# schema.net
KiCad netlist of a schematic drawn in Altium Designer
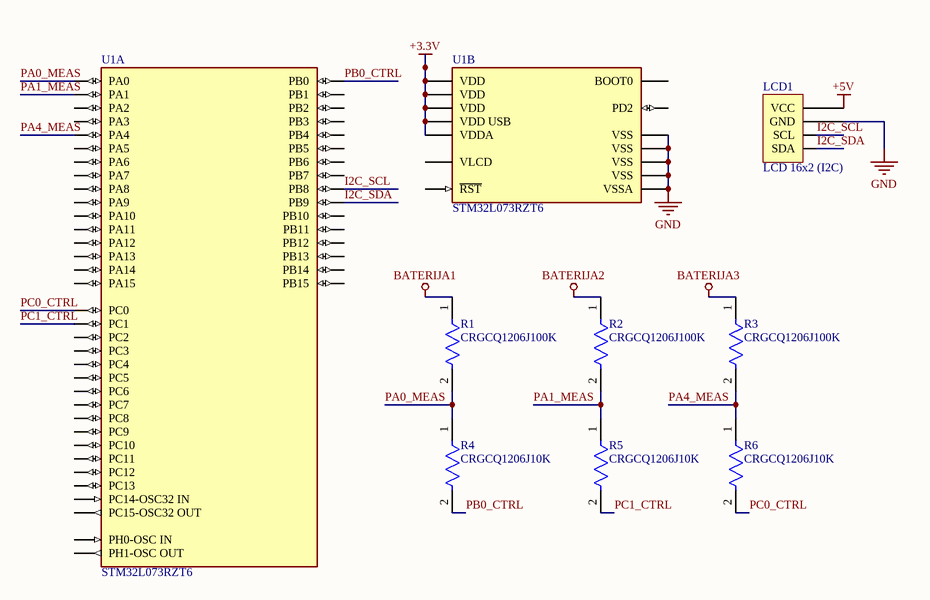
[diagram p0: schema.SchDoc]

(export (version "E")
  (design (tool "Eeschema 10.0.6"))
  (components
    (comp (ref "LCD1") (value "LCD 16x2 (I2C)") (libsource (lib "LCD") (part "LCD_I2C")))
    (comp (ref "R1")
      (value "CRGCQ1206J100K")
      (footprint "FP-CRGCQ1206-IPC_C")
      (description "CRGCQ1206 100KΩ 0.25W 5% ±100ppm/°C 200V")
      (fields
        (field (name "OCTOPART") "https://octopart.com/crgcq1206j100k-te+connectivity-91018303")
        (field (name "MANUFACTURER") "TE Connectivity")
      )
      (libsource (lib "Altium Content Vault") (part "1029c3af85768c4190bb7ad29bc67b5"))
    )
    (comp (ref "R2")
      (value "CRGCQ1206J100K")
      (footprint "FP-CRGCQ1206-IPC_C")
      (description "CRGCQ1206 100KΩ 0.25W 5% ±100ppm/°C 200V")
      (fields
        (field (name "OCTOPART") "https://octopart.com/crgcq1206j100k-te+connectivity-91018303")
        (field (name "MANUFACTURER") "TE Connectivity")
      )
      (libsource (lib "Altium Content Vault") (part "1029c3af85768c4190bb7ad29bc67b5"))
    )
    (comp (ref "R3")
      (value "CRGCQ1206J100K")
      (footprint "FP-CRGCQ1206-IPC_C")
      (description "CRGCQ1206 100KΩ 0.25W 5% ±100ppm/°C 200V")
      (fields
        (field (name "OCTOPART") "https://octopart.com/crgcq1206j100k-te+connectivity-91018303")
        (field (name "MANUFACTURER") "TE Connectivity")
      )
      (libsource (lib "Altium Content Vault") (part "1029c3af85768c4190bb7ad29bc67b5"))
    )
    (comp (ref "R4")
      (value "CRGCQ1206J10K")
      (footprint "FP-CRGCQ1206-IPC_C")
      (description "CRGCQ1206 10KΩ 0.25W 5% ±100ppm/°C 200V")
      (fields (field (name "MANUFACTURER") "TE Connectivity") (field (name "TOLERANCE") "0.05"))
      (libsource (lib "Altium Content Vault") (part "1029c3af85768c4190bb7ad29bc67b5"))
    )
    (comp (ref "R5")
      (value "CRGCQ1206J10K")
      (footprint "FP-CRGCQ1206-IPC_C")
      (description "CRGCQ1206 10KΩ 0.25W 5% ±100ppm/°C 200V")
      (fields (field (name "MANUFACTURER") "TE Connectivity") (field (name "TOLERANCE") "0.05"))
      (libsource (lib "Altium Content Vault") (part "1029c3af85768c4190bb7ad29bc67b5"))
    )
    (comp (ref "R6")
      (value "CRGCQ1206J10K")
      (footprint "FP-CRGCQ1206-IPC_C")
      (description "CRGCQ1206 10KΩ 0.25W 5% ±100ppm/°C 200V")
      (fields (field (name "MANUFACTURER") "TE Connectivity") (field (name "TOLERANCE") "0.05"))
      (libsource (lib "Altium Content Vault") (part "1029c3af85768c4190bb7ad29bc67b5"))
    )
    (comp (ref "U1")
      (value "STM32L073RZT6")
      (footprint "FP-LQFP64-5W-MFG")
      (description "IC MCU 32BIT 192KB FLASH 64LQFP")
      (libsource (lib "Altium Content Vault") (part "4466eda20ed5015702b21cb01f06cb7"))
    )
  )
  (nets
    (net (code "1") (name "+3.3V") (class "Default")
      (node (ref "U1") (pin "13") (pinfunction "VDDA_13") (pintype "power_in"))
      (node (ref "U1") (pin "19") (pinfunction "VDD_19") (pintype "power_in"))
      (node (ref "U1") (pin "32") (pinfunction "VDD_32") (pintype "power_in"))
      (node (ref "U1") (pin "48") (pinfunction "VDD_USB_48") (pintype "power_in"))
      (node (ref "U1") (pin "64") (pinfunction "VDD_64") (pintype "power_in"))
    )
    (net (code "2") (name "+5V") (class "Default")
      (node (ref "LCD1") (pin "1") (pinfunction "VCC_1") (pintype "passive"))
    )
    (net (code "3") (name "/I2C_SCL") (class "Default")
      (node (ref "LCD1") (pin "3") (pinfunction "SCL_3") (pintype "passive"))
      (node (ref "U1") (pin "61") (pinfunction "PB8_61") (pintype "bidirectional"))
    )
    (net (code "4") (name "/I2C_SDA") (class "Default")
      (node (ref "LCD1") (pin "4") (pinfunction "SDA_4") (pintype "passive"))
      (node (ref "U1") (pin "62") (pinfunction "PB9_62") (pintype "bidirectional"))
    )
    (net (code "5") (name "/PA0_MEAS") (class "Default")
      (node (ref "R1") (pin "2") (pinfunction "2_2") (pintype "passive"))
      (node (ref "R4") (pin "1") (pinfunction "1_1") (pintype "passive"))
      (node (ref "U1") (pin "14") (pinfunction "PA0_14") (pintype "bidirectional"))
    )
    (net (code "6") (name "/PA1_MEAS") (class "Default")
      (node (ref "R2") (pin "2") (pinfunction "2_2") (pintype "passive"))
      (node (ref "R5") (pin "1") (pinfunction "1_1") (pintype "passive"))
      (node (ref "U1") (pin "15") (pinfunction "PA1_15") (pintype "bidirectional"))
    )
    (net (code "7") (name "/PA4_MEAS") (class "Default")
      (node (ref "R3") (pin "2") (pinfunction "2_2") (pintype "passive"))
      (node (ref "R6") (pin "1") (pinfunction "1_1") (pintype "passive"))
      (node (ref "U1") (pin "20") (pinfunction "PA4_20") (pintype "bidirectional"))
    )
    (net (code "8") (name "/PB0_CTRL") (class "Default")
      (node (ref "R4") (pin "2") (pinfunction "2_2") (pintype "passive"))
      (node (ref "U1") (pin "26") (pinfunction "PB0_26") (pintype "bidirectional"))
    )
    (net (code "9") (name "/PC0_CTRL") (class "Default")
      (node (ref "R6") (pin "2") (pinfunction "2_2") (pintype "passive"))
      (node (ref "U1") (pin "8") (pinfunction "PC0_8") (pintype "bidirectional"))
    )
    (net (code "10") (name "/PC1_CTRL") (class "Default")
      (node (ref "R5") (pin "2") (pinfunction "2_2") (pintype "passive"))
      (node (ref "U1") (pin "9") (pinfunction "PC1_9") (pintype "bidirectional"))
    )
    (net (code "11") (name "BATERIJA1") (class "Default")
      (node (ref "R1") (pin "1") (pinfunction "1_1") (pintype "passive"))
    )
    (net (code "12") (name "BATERIJA2") (class "Default")
      (node (ref "R2") (pin "1") (pinfunction "1_1") (pintype "passive"))
    )
    (net (code "13") (name "BATERIJA3") (class "Default")
      (node (ref "R3") (pin "1") (pinfunction "1_1") (pintype "passive"))
    )
    (net (code "14") (name "GND") (class "Default")
      (node (ref "LCD1") (pin "2") (pinfunction "GND_2") (pintype "passive"))
      (node (ref "U1") (pin "12") (pinfunction "VSSA_12") (pintype "power_in"))
      (node (ref "U1") (pin "18") (pinfunction "VSS_18") (pintype "power_in"))
      (node (ref "U1") (pin "31") (pinfunction "VSS_31") (pintype "power_in"))
      (node (ref "U1") (pin "47") (pinfunction "VSS_47") (pintype "power_in"))
      (node (ref "U1") (pin "63") (pinfunction "VSS_63") (pintype "power_in"))
    )
    (net (code "15") (name "unconnected-(U1A-PA2-Pad16)") (class "Default")
      (node (ref "U1") (pin "16") (pinfunction "PA2_16") (pintype "bidirectional"))
    )
    (net (code "16") (name "unconnected-(U1A-PA3-Pad17)") (class "Default")
      (node (ref "U1") (pin "17") (pinfunction "PA3_17") (pintype "bidirectional"))
    )
    (net (code "17") (name "unconnected-(U1A-PA5-Pad21)") (class "Default")
      (node (ref "U1") (pin "21") (pinfunction "PA5_21") (pintype "bidirectional"))
    )
    (net (code "18") (name "unconnected-(U1A-PA6-Pad22)") (class "Default")
      (node (ref "U1") (pin "22") (pinfunction "PA6_22") (pintype "bidirectional"))
    )
    (net (code "19") (name "unconnected-(U1A-PA7-Pad23)") (class "Default")
      (node (ref "U1") (pin "23") (pinfunction "PA7_23") (pintype "bidirectional"))
    )
    (net (code "20") (name "unconnected-(U1A-PA8-Pad41)") (class "Default")
      (node (ref "U1") (pin "41") (pinfunction "PA8_41") (pintype "bidirectional"))
    )
    (net (code "21") (name "unconnected-(U1A-PA9-Pad42)") (class "Default")
      (node (ref "U1") (pin "42") (pinfunction "PA9_42") (pintype "bidirectional"))
    )
    (net (code "22") (name "unconnected-(U1A-PA10-Pad43)") (class "Default")
      (node (ref "U1") (pin "43") (pinfunction "PA10_43") (pintype "bidirectional"))
    )
    (net (code "23") (name "unconnected-(U1A-PA11-Pad44)") (class "Default")
      (node (ref "U1") (pin "44") (pinfunction "PA11_44") (pintype "bidirectional"))
    )
    (net (code "24") (name "unconnected-(U1A-PA12-Pad45)") (class "Default")
      (node (ref "U1") (pin "45") (pinfunction "PA12_45") (pintype "bidirectional"))
    )
    (net (code "25") (name "unconnected-(U1A-PA13-Pad46)") (class "Default")
      (node (ref "U1") (pin "46") (pinfunction "PA13_46") (pintype "bidirectional"))
    )
    (net (code "26") (name "unconnected-(U1A-PA14-Pad49)") (class "Default")
      (node (ref "U1") (pin "49") (pinfunction "PA14_49") (pintype "bidirectional"))
    )
    (net (code "27") (name "unconnected-(U1A-PA15-Pad50)") (class "Default")
      (node (ref "U1") (pin "50") (pinfunction "PA15_50") (pintype "bidirectional"))
    )
    (net (code "28") (name "unconnected-(U1A-PB1-Pad27)") (class "Default")
      (node (ref "U1") (pin "27") (pinfunction "PB1_27") (pintype "bidirectional"))
    )
    (net (code "29") (name "unconnected-(U1A-PB2-Pad28)") (class "Default")
      (node (ref "U1") (pin "28") (pinfunction "PB2_28") (pintype "bidirectional"))
    )
    (net (code "30") (name "unconnected-(U1A-PB3-Pad55)") (class "Default")
      (node (ref "U1") (pin "55") (pinfunction "PB3_55") (pintype "bidirectional"))
    )
    (net (code "31") (name "unconnected-(U1A-PB4-Pad56)") (class "Default")
      (node (ref "U1") (pin "56") (pinfunction "PB4_56") (pintype "bidirectional"))
    )
    (net (code "32") (name "unconnected-(U1A-PB5-Pad57)") (class "Default")
      (node (ref "U1") (pin "57") (pinfunction "PB5_57") (pintype "bidirectional"))
    )
    (net (code "33") (name "unconnected-(U1A-PB6-Pad58)") (class "Default")
      (node (ref "U1") (pin "58") (pinfunction "PB6_58") (pintype "bidirectional"))
    )
    (net (code "34") (name "unconnected-(U1A-PB7-Pad59)") (class "Default")
      (node (ref "U1") (pin "59") (pinfunction "PB7_59") (pintype "bidirectional"))
    )
    (net (code "35") (name "unconnected-(U1A-PB10-Pad29)") (class "Default")
      (node (ref "U1") (pin "29") (pinfunction "PB10_29") (pintype "bidirectional"))
    )
    (net (code "36") (name "unconnected-(U1A-PB11-Pad30)") (class "Default")
      (node (ref "U1") (pin "30") (pinfunction "PB11_30") (pintype "bidirectional"))
    )
    (net (code "37") (name "unconnected-(U1A-PB12-Pad33)") (class "Default")
      (node (ref "U1") (pin "33") (pinfunction "PB12_33") (pintype "bidirectional"))
    )
    (net (code "38") (name "unconnected-(U1A-PB13-Pad34)") (class "Default")
      (node (ref "U1") (pin "34") (pinfunction "PB13_34") (pintype "bidirectional"))
    )
    (net (code "39") (name "unconnected-(U1A-PB14-Pad35)") (class "Default")
      (node (ref "U1") (pin "35") (pinfunction "PB14_35") (pintype "bidirectional"))
    )
    (net (code "40") (name "unconnected-(U1A-PB15-Pad36)") (class "Default")
      (node (ref "U1") (pin "36") (pinfunction "PB15_36") (pintype "bidirectional"))
    )
    (net (code "41") (name "unconnected-(U1A-PC2-Pad10)") (class "Default")
      (node (ref "U1") (pin "10") (pinfunction "PC2_10") (pintype "bidirectional"))
    )
    (net (code "42") (name "unconnected-(U1A-PC3-Pad11)") (class "Default")
      (node (ref "U1") (pin "11") (pinfunction "PC3_11") (pintype "bidirectional"))
    )
    (net (code "43") (name "unconnected-(U1A-PC4-Pad24)") (class "Default")
      (node (ref "U1") (pin "24") (pinfunction "PC4_24") (pintype "bidirectional"))
    )
    (net (code "44") (name "unconnected-(U1A-PC5-Pad25)") (class "Default")
      (node (ref "U1") (pin "25") (pinfunction "PC5_25") (pintype "bidirectional"))
    )
    (net (code "45") (name "unconnected-(U1A-PC6-Pad37)") (class "Default")
      (node (ref "U1") (pin "37") (pinfunction "PC6_37") (pintype "bidirectional"))
    )
    (net (code "46") (name "unconnected-(U1A-PC7-Pad38)") (class "Default")
      (node (ref "U1") (pin "38") (pinfunction "PC7_38") (pintype "bidirectional"))
    )
    (net (code "47") (name "unconnected-(U1A-PC8-Pad39)") (class "Default")
      (node (ref "U1") (pin "39") (pinfunction "PC8_39") (pintype "bidirectional"))
    )
    (net (code "48") (name "unconnected-(U1A-PC9-Pad40)") (class "Default")
      (node (ref "U1") (pin "40") (pinfunction "PC9_40") (pintype "bidirectional"))
    )
    (net (code "49") (name "unconnected-(U1A-PC10-Pad51)") (class "Default")
      (node (ref "U1") (pin "51") (pinfunction "PC10_51") (pintype "bidirectional"))
    )
    (net (code "50") (name "unconnected-(U1A-PC11-Pad52)") (class "Default")
      (node (ref "U1") (pin "52") (pinfunction "PC11_52") (pintype "bidirectional"))
    )
    (net (code "51") (name "unconnected-(U1A-PC12-Pad53)") (class "Default")
      (node (ref "U1") (pin "53") (pinfunction "PC12_53") (pintype "bidirectional"))
    )
    (net (code "52") (name "unconnected-(U1A-PC13-Pad2)") (class "Default")
      (node (ref "U1") (pin "2") (pinfunction "PC13_2") (pintype "bidirectional"))
    )
    (net (code "53") (name "unconnected-(U1A-PC14-OSC32_IN-Pad3)") (class "Default")
      (node (ref "U1") (pin "3") (pinfunction "PC14-OSC32_IN_3") (pintype "input"))
    )
    (net (code "54") (name "unconnected-(U1A-PC15-OSC32_OUT-Pad4)") (class "Default")
      (node (ref "U1") (pin "4") (pinfunction "PC15-OSC32_OUT_4") (pintype "output"))
    )
    (net (code "55") (name "unconnected-(U1A-PH0-OSC_IN-Pad5)") (class "Default")
      (node (ref "U1") (pin "5") (pinfunction "PH0-OSC_IN_5") (pintype "input"))
    )
    (net (code "56") (name "unconnected-(U1A-PH1-OSC_OUT-Pad6)") (class "Default")
      (node (ref "U1") (pin "6") (pinfunction "PH1-OSC_OUT_6") (pintype "output"))
    )
    (net (code "57") (name "unconnected-(U1B-BOOT0-Pad60)") (class "Default")
      (node (ref "U1") (pin "60") (pinfunction "BOOT0_60") (pintype "passive"))
    )
    (net (code "58") (name "unconnected-(U1B-PD2-Pad54)") (class "Default")
      (node (ref "U1") (pin "54") (pinfunction "PD2_54") (pintype "bidirectional"))
    )
    (net (code "59") (name "unconnected-(U1B-VLCD-Pad1)") (class "Default")
      (node (ref "U1") (pin "1") (pinfunction "VLCD_1") (pintype "power_in"))
    )
    (net (code "60") (name "unconnected-(U1B-~{RST}-Pad7)") (class "Default")
      (node (ref "U1") (pin "7") (pinfunction "~{RST}_7") (pintype "input"))
    )
  )
)
